# design.net
KiCad netlist of a schematic drawn in Altium Designer
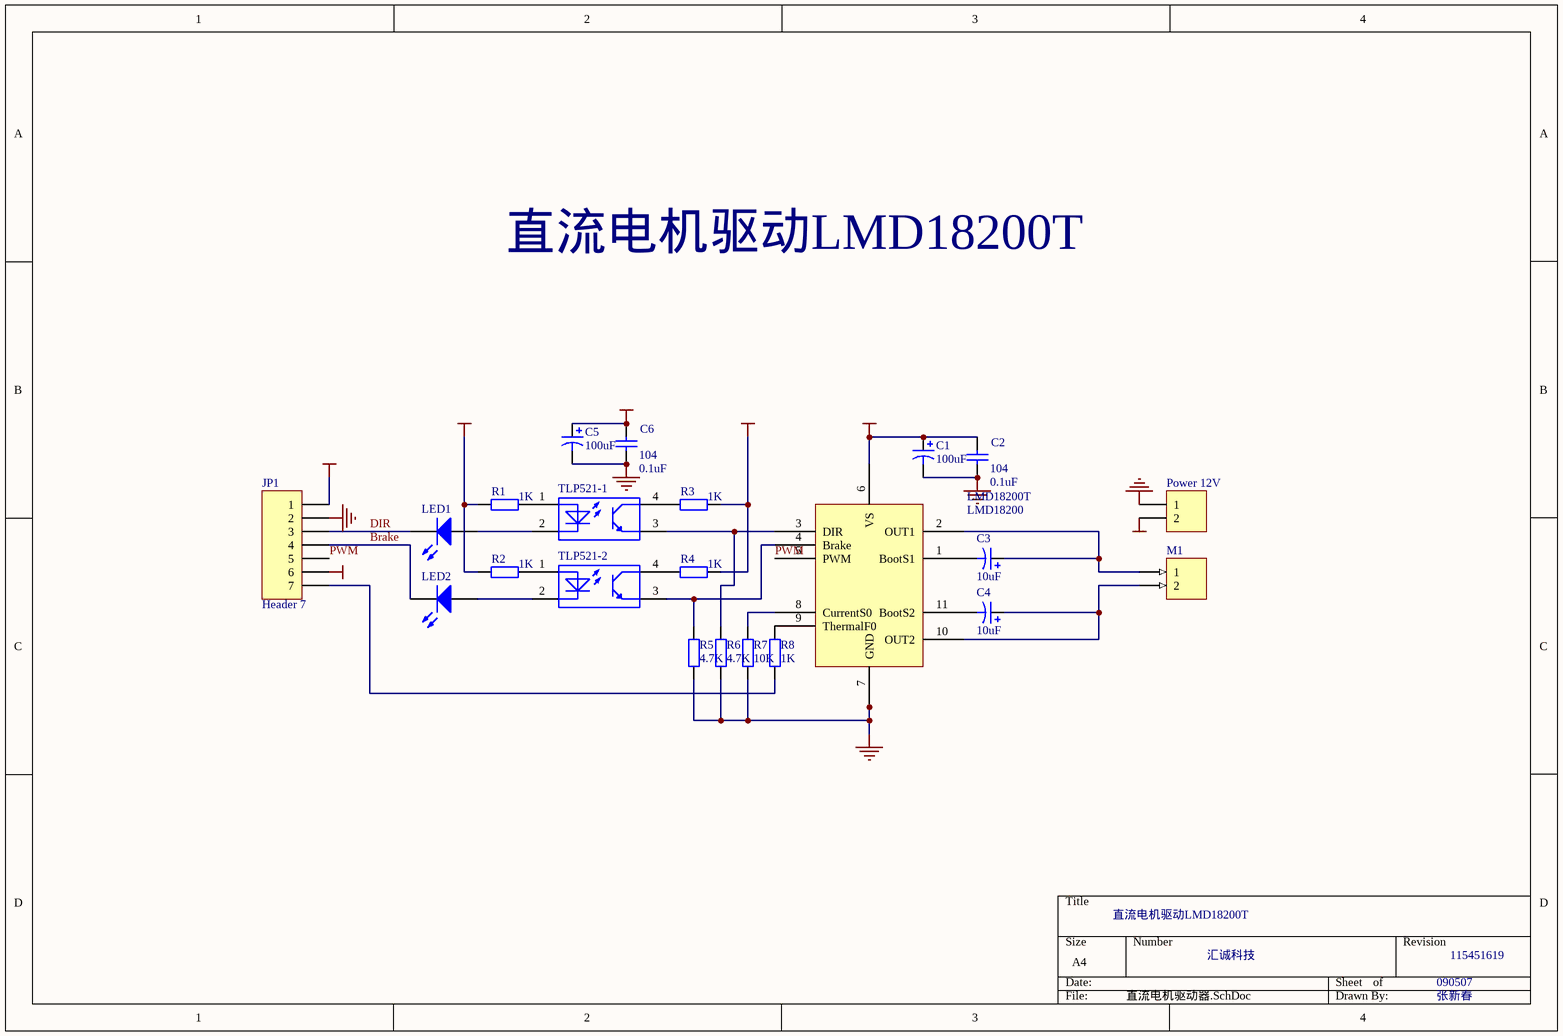
[diagram p0: 直流电机驱动器.SchDoc]

(export (version "E")
  (design (tool "Eeschema 10.0.6"))
  (components
    (comp (ref "C1")
      (value "100uF")
      (footprint "DJDR_8mm")
      (description "Polarized Capacitor (Surface Mount)")
      (fields (field (name "PUBLISHER") "Altium Limited"))
      (libsource (lib "Miscellaneous Devices") (part "Cap Pol3"))
    )
    (comp (ref "C2")
      (value "104")
      (footprint "CPDR")
      (description "Capacitor")
      (fields (field (name "ALTIUM_VALUE") "0.1uF") (field (name "PUBLISHER") "Altium Limited"))
      (libsource (lib "Miscellaneous Devices") (part "Cap"))
    )
    (comp (ref "C3")
      (value "10uF")
      (footprint "DJDR_4mm")
      (description "Polarized Capacitor (Surface Mount)")
      (fields (field (name "PUBLISHER") "Altium Limited"))
      (libsource (lib "Miscellaneous Devices") (part "Cap Pol3"))
    )
    (comp (ref "C4")
      (value "10uF")
      (footprint "DJDR_4mm")
      (description "Polarized Capacitor (Surface Mount)")
      (fields (field (name "PUBLISHER") "Altium Limited"))
      (libsource (lib "Miscellaneous Devices") (part "Cap Pol3"))
    )
    (comp (ref "C5")
      (value "100uF")
      (footprint "DJDR_8mm")
      (description "Polarized Capacitor (Surface Mount)")
      (fields (field (name "PUBLISHER") "Altium Limited"))
      (libsource (lib "Miscellaneous Devices") (part "Cap Pol3"))
    )
    (comp (ref "C6")
      (value "104")
      (footprint "CPDR")
      (description "Capacitor")
      (fields (field (name "ALTIUM_VALUE") "0.1uF") (field (name "PUBLISHER") "Altium Limited"))
      (libsource (lib "Miscellaneous Devices") (part "Cap"))
    )
    (comp (ref "JP1")
      (value "Header 7")
      (footprint "HDR1X7")
      (description "Header, 7-Pin")
      (fields (field (name "PUBLISHER") "Altium Limited"))
      (libsource (lib "Miscellaneous Connectors") (part "Header 7"))
    )
    (comp (ref "LED1")
      (value "~")
      (footprint "HDR1X2")
      (description "Typical BLUE SiC LED")
      (fields (field (name "PUBLISHER") "Altium Limited"))
      (libsource (lib "Miscellaneous Devices") (part "LED3"))
    )
    (comp (ref "LED2")
      (value "~")
      (footprint "HDR1X2")
      (description "Typical BLUE SiC LED")
      (fields (field (name "PUBLISHER") "Altium Limited"))
      (libsource (lib "Miscellaneous Devices") (part "LED3"))
    )
    (comp (ref "LMD18200T")
      (value "LMD18200")
      (footprint "LMD18200T")
      (libsource (lib "LMD18200") (part "LMD18200"))
    )
    (comp (ref "M1")
      (value "~")
      (footprint "JK128")
      (description "Header, 2-Pin")
      (fields (field (name "PUBLISHER") "Altium Limited"))
      (libsource (lib "Miscellaneous Connectors") (part "MHDR1X2"))
    )
    (comp (ref "Power 12V")
      (value "~")
      (footprint "JK128")
      (description "Header, 2-Pin")
      (fields (field (name "PUBLISHER") "Altium Limited"))
      (libsource (lib "Miscellaneous Connectors") (part "MHDR1X2"))
    )
    (comp (ref "R1")
      (value "1K")
      (footprint "HDR-2")
      (description "Resistor")
      (fields (field (name "PUBLISHER") "Altium Limited"))
      (libsource (lib "") (part "Res2_1"))
    )
    (comp (ref "R2")
      (value "1K")
      (footprint "HDR-2")
      (description "Resistor")
      (fields (field (name "PUBLISHER") "Altium Limited"))
      (libsource (lib "") (part "Res2_1"))
    )
    (comp (ref "R3")
      (value "1K")
      (footprint "HDR-2")
      (description "Resistor")
      (fields (field (name "PUBLISHER") "Altium Limited"))
      (libsource (lib "") (part "Res2_1"))
    )
    (comp (ref "R4")
      (value "1K")
      (footprint "HDR-2")
      (description "Resistor")
      (fields (field (name "PUBLISHER") "Altium Limited"))
      (libsource (lib "") (part "Res2_1"))
    )
    (comp (ref "R5")
      (value "4.7K")
      (footprint "HDR-2")
      (description "Resistor")
      (fields (field (name "PUBLISHER") "Altium Limited"))
      (libsource (lib "") (part "Res2_2"))
    )
    (comp (ref "R6")
      (value "4.7K")
      (footprint "HDR-2")
      (description "Resistor")
      (fields (field (name "PUBLISHER") "Altium Limited"))
      (libsource (lib "") (part "Res2_2"))
    )
    (comp (ref "R7")
      (value "10K")
      (footprint "HDR-2")
      (description "Resistor")
      (fields (field (name "PUBLISHER") "Altium Limited"))
      (libsource (lib "") (part "Res2_2"))
    )
    (comp (ref "R8")
      (value "1K")
      (footprint "HDR-2")
      (description "Resistor")
      (fields (field (name "PUBLISHER") "Altium Limited"))
      (libsource (lib "Miscellaneous Devices") (part "Res2"))
    )
    (comp (ref "TLP521-1") (value "~") (footprint "DIP-4") (libsource (lib "MyInt_Lib") (part "TLP521-1")))
    (comp (ref "TLP521-2") (value "~") (footprint "DIP-4") (libsource (lib "MyInt_Lib") (part "TLP521-1")))
  )
  (nets
    (net (code "1") (name "+5V") (class "Default")
      (node (ref "C5") (pin "1") (pinfunction "1_1") (pintype "passive"))
      (node (ref "C6") (pin "2") (pinfunction "2_2") (pintype "passive"))
      (node (ref "JP1") (pin "1") (pinfunction "1_1") (pintype "passive"))
      (node (ref "JP1") (pin "6") (pinfunction "6_6") (pintype "passive"))
      (node (ref "R1") (pin "1") (pinfunction "1_1") (pintype "passive"))
      (node (ref "R2") (pin "1") (pinfunction "1_1") (pintype "passive"))
      (node (ref "R3") (pin "2") (pinfunction "2_2") (pintype "passive"))
      (node (ref "R4") (pin "2") (pinfunction "2_2") (pintype "passive"))
    )
    (net (code "2") (name "/Brake") (class "Default")
      (node (ref "JP1") (pin "4") (pinfunction "4_4") (pintype "passive"))
      (node (ref "LED2") (pin "2") (pinfunction "K_2") (pintype "passive"))
    )
    (net (code "3") (name "/DIR") (class "Default")
      (node (ref "JP1") (pin "3") (pinfunction "3_3") (pintype "passive"))
      (node (ref "LED1") (pin "2") (pinfunction "K_2") (pintype "passive"))
    )
    (net (code "4") (name "/PWM") (class "Default")
      (node (ref "JP1") (pin "5") (pinfunction "5_5") (pintype "passive"))
      (node (ref "LMD18200T") (pin "5") (pinfunction "PWM_5") (pintype "passive"))
    )
    (net (code "5") (name "GND") (class "Default")
      (node (ref "C1") (pin "2") (pinfunction "2_2") (pintype "passive"))
      (node (ref "C2") (pin "1") (pinfunction "1_1") (pintype "passive"))
      (node (ref "C5") (pin "2") (pinfunction "2_2") (pintype "passive"))
      (node (ref "C6") (pin "1") (pinfunction "1_1") (pintype "passive"))
      (node (ref "JP1") (pin "2") (pinfunction "2_2") (pintype "passive"))
      (node (ref "LMD18200T") (pin "7") (pinfunction "GND_7") (pintype "passive"))
      (node (ref "Power 12V") (pin "1") (pinfunction "1_1") (pintype "input"))
      (node (ref "R5") (pin "1") (pinfunction "1_1") (pintype "passive"))
      (node (ref "R6") (pin "1") (pinfunction "1_1") (pintype "passive"))
      (node (ref "R7") (pin "1") (pinfunction "1_1") (pintype "passive"))
    )
    (net (code "6") (name "Net-(JP1-Pad7)") (class "Default")
      (node (ref "JP1") (pin "7") (pinfunction "7_7") (pintype "passive"))
      (node (ref "R8") (pin "2") (pinfunction "2_2") (pintype "passive"))
    )
    (net (code "7") (name "Net-(LED1-A)") (class "Default")
      (node (ref "LED1") (pin "1") (pinfunction "A_1") (pintype "passive"))
      (node (ref "TLP521-1") (pin "2") (pinfunction "2_2") (pintype "passive"))
    )
    (net (code "8") (name "Net-(LED2-A)") (class "Default")
      (node (ref "LED2") (pin "1") (pinfunction "A_1") (pintype "passive"))
      (node (ref "TLP521-2") (pin "2") (pinfunction "2_2") (pintype "passive"))
    )
    (net (code "9") (name "Net-(LMD18200T-BootS1)") (class "Default")
      (node (ref "C3") (pin "2") (pinfunction "2_2") (pintype "passive"))
      (node (ref "LMD18200T") (pin "1") (pinfunction "BootS1_1") (pintype "passive"))
    )
    (net (code "10") (name "Net-(LMD18200T-BootS2)") (class "Default")
      (node (ref "C4") (pin "2") (pinfunction "2_2") (pintype "passive"))
      (node (ref "LMD18200T") (pin "11") (pinfunction "BootS2_11") (pintype "passive"))
    )
    (net (code "11") (name "Net-(LMD18200T-Brake)") (class "Default")
      (node (ref "LMD18200T") (pin "4") (pinfunction "Brake_4") (pintype "passive"))
      (node (ref "R5") (pin "2") (pinfunction "2_2") (pintype "passive"))
      (node (ref "TLP521-2") (pin "3") (pinfunction "3_3") (pintype "passive"))
    )
    (net (code "12") (name "Net-(LMD18200T-CurrentS0)") (class "Default")
      (node (ref "LMD18200T") (pin "8") (pinfunction "CurrentS0_8") (pintype "passive"))
      (node (ref "R7") (pin "2") (pinfunction "2_2") (pintype "passive"))
    )
    (net (code "13") (name "Net-(LMD18200T-DIR)") (class "Default")
      (node (ref "LMD18200T") (pin "3") (pinfunction "DIR_3") (pintype "passive"))
      (node (ref "R6") (pin "2") (pinfunction "2_2") (pintype "passive"))
      (node (ref "TLP521-1") (pin "3") (pinfunction "3_3") (pintype "passive"))
    )
    (net (code "14") (name "Net-(LMD18200T-OUT1)") (class "Default")
      (node (ref "C3") (pin "1") (pinfunction "1_1") (pintype "passive"))
      (node (ref "LMD18200T") (pin "2") (pinfunction "OUT1_2") (pintype "passive"))
      (node (ref "M1") (pin "1") (pinfunction "1_1") (pintype "input"))
    )
    (net (code "15") (name "Net-(LMD18200T-OUT2)") (class "Default")
      (node (ref "C4") (pin "1") (pinfunction "1_1") (pintype "passive"))
      (node (ref "LMD18200T") (pin "10") (pinfunction "OUT2_10") (pintype "passive"))
      (node (ref "M1") (pin "2") (pinfunction "2_2") (pintype "input"))
    )
    (net (code "16") (name "Net-(LMD18200T-ThermalF0)") (class "Default")
      (node (ref "LMD18200T") (pin "9") (pinfunction "ThermalF0_9") (pintype "passive"))
      (node (ref "R8") (pin "1") (pinfunction "1_1") (pintype "passive"))
    )
    (net (code "17") (name "Net-(R1-Pad2)") (class "Default")
      (node (ref "R1") (pin "2") (pinfunction "2_2") (pintype "passive"))
      (node (ref "TLP521-1") (pin "1") (pinfunction "1_1") (pintype "passive"))
    )
    (net (code "18") (name "Net-(R2-Pad2)") (class "Default")
      (node (ref "R2") (pin "2") (pinfunction "2_2") (pintype "passive"))
      (node (ref "TLP521-2") (pin "1") (pinfunction "1_1") (pintype "passive"))
    )
    (net (code "19") (name "Net-(R3-Pad1)") (class "Default")
      (node (ref "R3") (pin "1") (pinfunction "1_1") (pintype "passive"))
      (node (ref "TLP521-1") (pin "4") (pinfunction "4_4") (pintype "passive"))
    )
    (net (code "20") (name "Net-(R4-Pad1)") (class "Default")
      (node (ref "R4") (pin "1") (pinfunction "1_1") (pintype "passive"))
      (node (ref "TLP521-2") (pin "4") (pinfunction "4_4") (pintype "passive"))
    )
    (net (code "21") (name "VS") (class "Default")
      (node (ref "C1") (pin "1") (pinfunction "1_1") (pintype "passive"))
      (node (ref "C2") (pin "2") (pinfunction "2_2") (pintype "passive"))
      (node (ref "LMD18200T") (pin "6") (pinfunction "VS_6") (pintype "passive"))
      (node (ref "Power 12V") (pin "2") (pinfunction "2_2") (pintype "input"))
    )
  )
)
